# Adafruit_S-35710_Breakout.net
KiCad netlist of a schematic drawn in EAGLE
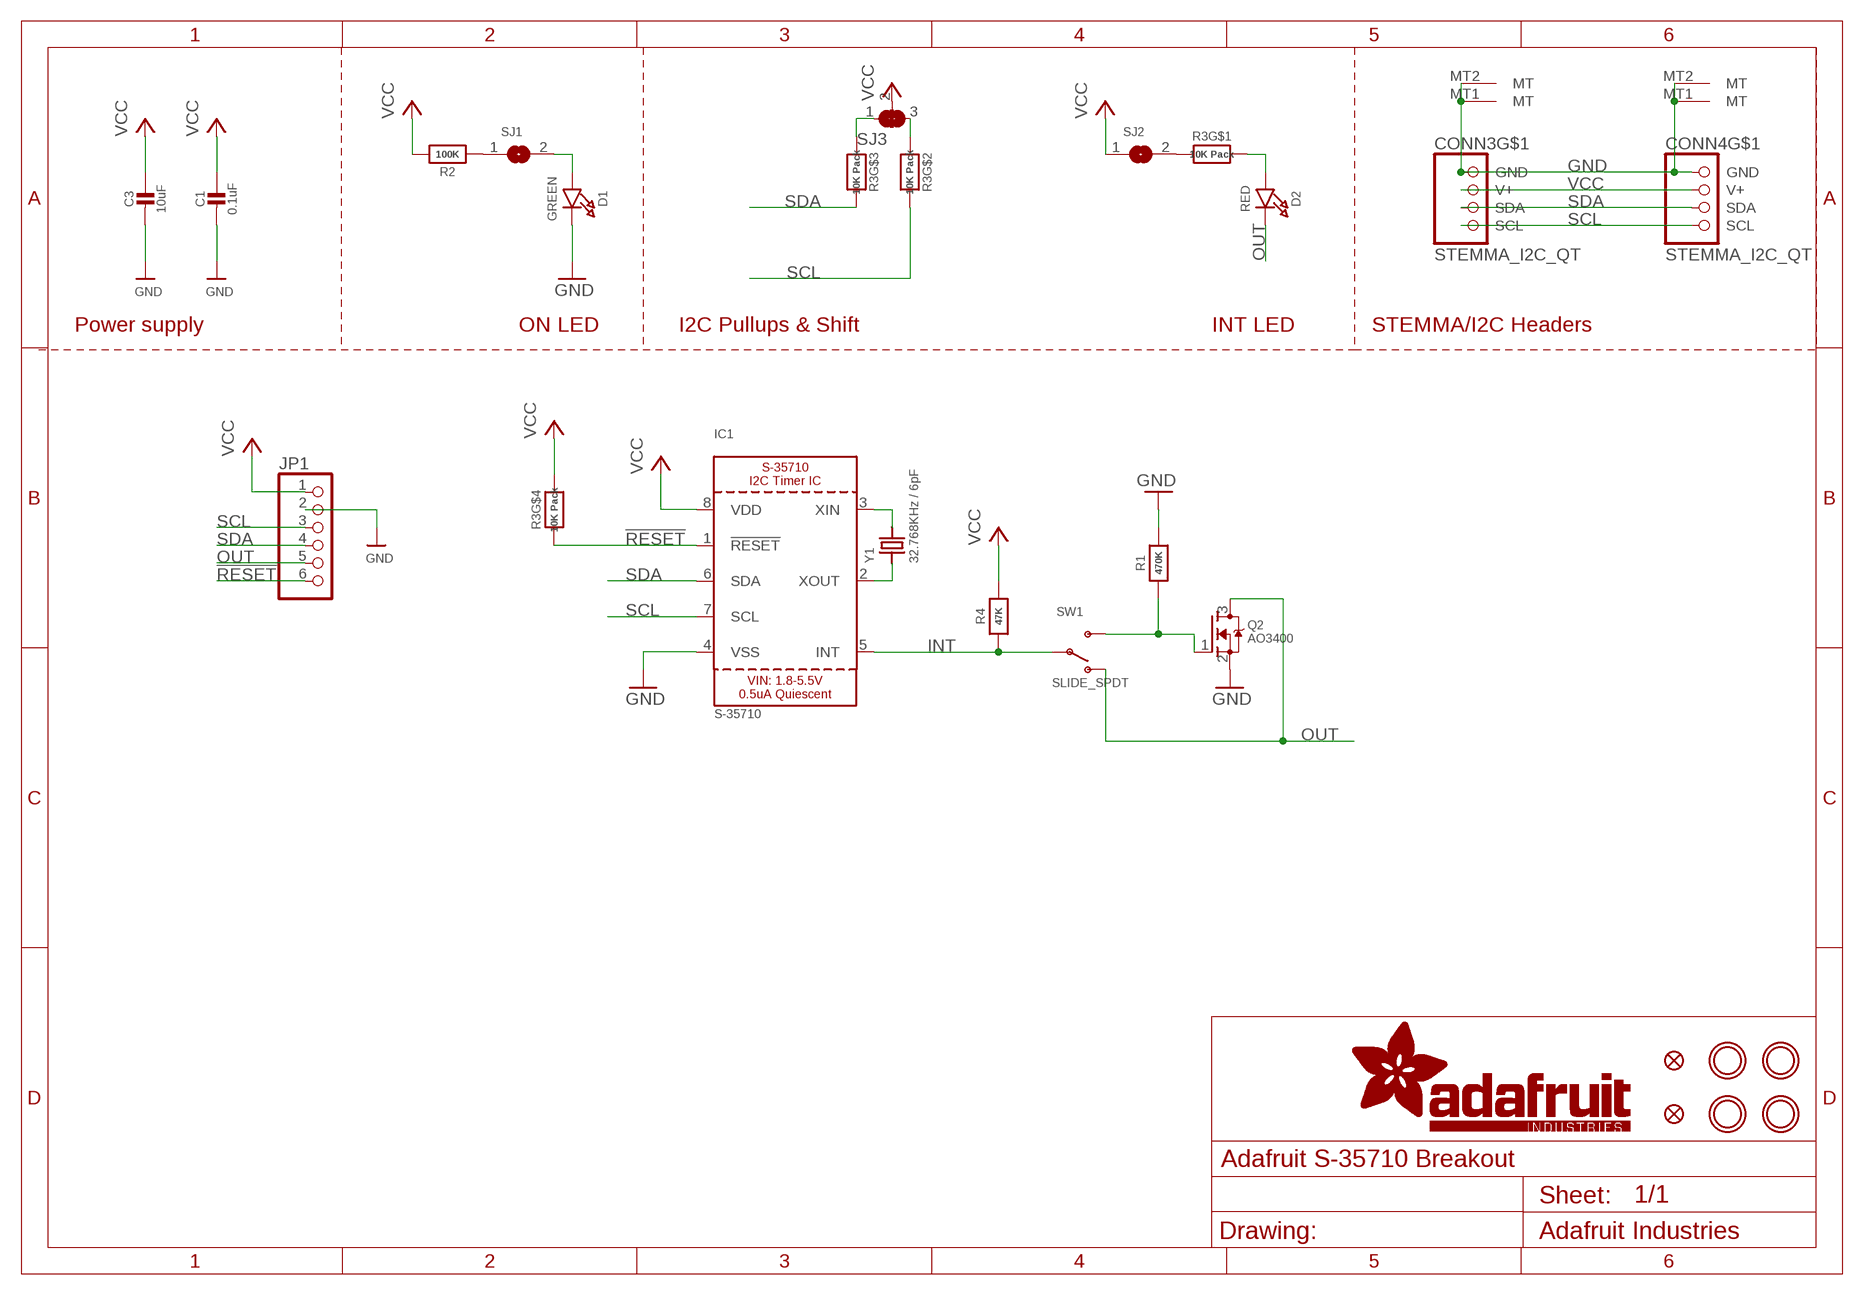
[diagram p0: schematic, sheet 1]

(export (version "E")
  (design (tool "Eeschema 10.0.6"))
  (components
    (comp (ref "C1")
      (value "0.1uF")
      (footprint "eagle-import:0603-NO")
      (libsource (lib "eagle-import") (part "CAP_CERAMIC0603_NO"))
    )
    (comp (ref "C3")
      (value "10uF")
      (footprint "eagle-import:0805-NO")
      (libsource (lib "eagle-import") (part "CAP_CERAMIC0805-NOOUTLINE"))
    )
    (comp (ref "CONN3")
      (value "STEMMA_I2C_QT")
      (footprint "eagle-import:JST_SH4")
      (libsource (lib "eagle-import") (part "STEMMA_I2C_QT"))
    )
    (comp (ref "CONN4")
      (value "STEMMA_I2C_QT")
      (footprint "eagle-import:JST_SH4")
      (libsource (lib "eagle-import") (part "STEMMA_I2C_QT"))
    )
    (comp (ref "D1")
      (value "GREEN")
      (footprint "eagle-import:CHIPLED_0603_NOOUTLINE")
      (libsource (lib "eagle-import") (part "LED0603_NOOUTLINE"))
    )
    (comp (ref "D2")
      (value "RED")
      (footprint "eagle-import:CHIPLED_0603_NOOUTLINE")
      (libsource (lib "eagle-import") (part "LED0603_NOOUTLINE"))
    )
    (comp (ref "FID3")
      (value "FIDUCIAL_1MM")
      (footprint "eagle-import:FIDUCIAL_1MM")
      (libsource (lib "eagle-import") (part "FIDUCIAL_1MM"))
    )
    (comp (ref "FID4")
      (value "FIDUCIAL_1MM")
      (footprint "eagle-import:FIDUCIAL_1MM")
      (libsource (lib "eagle-import") (part "FIDUCIAL_1MM"))
    )
    (comp (ref "IC1")
      (value "S-35710")
      (footprint "eagle-import:MSOP8_0.65MM")
      (libsource (lib "eagle-import") (part "S-35710"))
    )
    (comp (ref "JP1")
      (value "HEADER-1X670MIL")
      (footprint "eagle-import:1X06_ROUND_70")
      (libsource (lib "eagle-import") (part "HEADER-1X670MIL"))
    )
    (comp (ref "Q2")
      (value "AO3400")
      (footprint "eagle-import:SOT23-WIDE")
      (libsource (lib "eagle-import") (part "MOSFET-NWIDE"))
    )
    (comp (ref "R1")
      (value "470K")
      (footprint "eagle-import:0603-NO")
      (libsource (lib "eagle-import") (part "RESISTOR_0603_NOOUT"))
    )
    (comp (ref "R2")
      (value "100K")
      (footprint "eagle-import:0603-NO")
      (libsource (lib "eagle-import") (part "RESISTOR_0603_NOOUT"))
    )
    (comp (ref "R3")
      (value "10K Pack")
      (footprint "eagle-import:RESPACK_4X0603")
      (libsource (lib "eagle-import") (part "RESISTOR_4PACK"))
    )
    (comp (ref "R4")
      (value "47K")
      (footprint "eagle-import:0603-NO")
      (libsource (lib "eagle-import") (part "RESISTOR_0603_NOOUT"))
    )
    (comp (ref "SJ1")
      (value "SOLDERJUMPERCLOSED")
      (footprint "eagle-import:SOLDERJUMPER_CLOSEDWIRE")
      (libsource (lib "eagle-import") (part "SOLDERJUMPERCLOSED"))
    )
    (comp (ref "SJ2")
      (value "SOLDERJUMPERCLOSED")
      (footprint "eagle-import:SOLDERJUMPER_CLOSEDWIRE")
      (libsource (lib "eagle-import") (part "SOLDERJUMPERCLOSED"))
    )
    (comp (ref "SJ3")
      (value "SOLDERJUMPER_2WAY")
      (footprint "eagle-import:SOLDERJUMPER_2WAY_OPEN_NOPASTE")
      (libsource (lib "eagle-import") (part "SOLDERJUMPER_2WAY"))
    )
    (comp (ref "SW1")
      (value "SLIDE_SPDT")
      (footprint "eagle-import:SPDT_SMT_SSSS811101")
      (libsource (lib "eagle-import") (part "SWITCH_SPDT"))
    )
    (comp (ref "U$1")
      (value "MOUNTINGHOLE2.5")
      (footprint "eagle-import:MOUNTINGHOLE_2.5_PLATED")
      (libsource (lib "eagle-import") (part "MOUNTINGHOLE2.5"))
    )
    (comp (ref "U$17")
      (value "MOUNTINGHOLE2.5")
      (footprint "eagle-import:MOUNTINGHOLE_2.5_PLATED")
      (libsource (lib "eagle-import") (part "MOUNTINGHOLE2.5"))
    )
    (comp (ref "U$19")
      (value "MOUNTINGHOLE2.5")
      (footprint "eagle-import:MOUNTINGHOLE_2.5_PLATED")
      (libsource (lib "eagle-import") (part "MOUNTINGHOLE2.5"))
    )
    (comp (ref "U$21")
      (value "MOUNTINGHOLE2.5")
      (footprint "eagle-import:MOUNTINGHOLE_2.5_PLATED")
      (libsource (lib "eagle-import") (part "MOUNTINGHOLE2.5"))
    )
    (comp (ref "Y1")
      (value "32.768KHz / 6pF")
      (footprint "eagle-import:XTAL3215")
      (libsource (lib "eagle-import") (part "CRYSTAL_3215"))
    )
  )
  (nets
    (net (code "1") (name "/INT") (class "Default")
      (node (ref "IC1") (pin "5") (pinfunction "INT_5") (pintype "output"))
      (node (ref "R4") (pin "1") (pinfunction "1_1") (pintype "passive"))
      (node (ref "SW1") (pin "B") (pinfunction "P_B") (pintype "passive"))
    )
    (net (code "2") (name "/OUT") (class "Default")
      (node (ref "D2") (pin "C") (pinfunction "C_C") (pintype "passive"))
      (node (ref "JP1") (pin "5") (pinfunction "5_5") (pintype "passive"))
      (node (ref "Q2") (pin "3") (pinfunction "D_3") (pintype "bidirectional"))
      (node (ref "SW1") (pin "A") (pinfunction "O_A") (pintype "passive"))
    )
    (net (code "3") (name "/SCL") (class "Default")
      (node (ref "CONN3") (pin "4") (pinfunction "SCL_4") (pintype "passive"))
      (node (ref "CONN4") (pin "4") (pinfunction "SCL_4") (pintype "passive"))
      (node (ref "IC1") (pin "7") (pinfunction "SCL_7") (pintype "bidirectional"))
      (node (ref "JP1") (pin "3") (pinfunction "3_3") (pintype "passive"))
      (node (ref "R3") (pin "7") (pinfunction "2_7") (pintype "passive"))
    )
    (net (code "4") (name "/SDA") (class "Default")
      (node (ref "CONN3") (pin "3") (pinfunction "SDA_3") (pintype "passive"))
      (node (ref "CONN4") (pin "3") (pinfunction "SDA_3") (pintype "passive"))
      (node (ref "IC1") (pin "6") (pinfunction "SDA_6") (pintype "bidirectional"))
      (node (ref "JP1") (pin "4") (pinfunction "4_4") (pintype "passive"))
      (node (ref "R3") (pin "6") (pinfunction "2_6") (pintype "passive"))
    )
    (net (code "5") (name "/~{RESET}") (class "Default")
      (node (ref "IC1") (pin "1") (pinfunction "~{RESET}_1") (pintype "input"))
      (node (ref "JP1") (pin "6") (pinfunction "6_6") (pintype "passive"))
      (node (ref "R3") (pin "4") (pinfunction "1_4") (pintype "passive"))
    )
    (net (code "6") (name "GND") (class "Default")
      (node (ref "C1") (pin "2") (pinfunction "2_2") (pintype "passive"))
      (node (ref "C3") (pin "2") (pinfunction "2_2") (pintype "passive"))
      (node (ref "CONN3") (pin "1") (pinfunction "GND_1") (pintype "passive"))
      (node (ref "CONN3") (pin "MT1") (pinfunction "MT_MT1") (pintype "bidirectional"))
      (node (ref "CONN3") (pin "MT2") (pinfunction "MT_MT2") (pintype "bidirectional"))
      (node (ref "CONN4") (pin "1") (pinfunction "GND_1") (pintype "passive"))
      (node (ref "CONN4") (pin "MT1") (pinfunction "MT_MT1") (pintype "bidirectional"))
      (node (ref "CONN4") (pin "MT2") (pinfunction "MT_MT2") (pintype "bidirectional"))
      (node (ref "D1") (pin "C") (pinfunction "C_C") (pintype "passive"))
      (node (ref "IC1") (pin "4") (pinfunction "VSS_4") (pintype "power_in"))
      (node (ref "JP1") (pin "2") (pinfunction "2_2") (pintype "passive"))
      (node (ref "Q2") (pin "2") (pinfunction "S_2") (pintype "bidirectional"))
      (node (ref "R1") (pin "2") (pinfunction "2_2") (pintype "passive"))
    )
    (net (code "7") (name "Net-(D1-PadA)") (class "Default")
      (node (ref "D1") (pin "A") (pinfunction "A_A") (pintype "passive"))
      (node (ref "SJ1") (pin "2") (pinfunction "2_2") (pintype "passive"))
    )
    (net (code "8") (name "Net-(IC1-XIN)") (class "Default")
      (node (ref "IC1") (pin "3") (pinfunction "XIN_3") (pintype "input"))
      (node (ref "Y1") (pin "P$2") (pinfunction "2_P$2") (pintype "passive"))
    )
    (net (code "9") (name "Net-(IC1-XOUT)") (class "Default")
      (node (ref "IC1") (pin "2") (pinfunction "XOUT_2") (pintype "input"))
      (node (ref "Y1") (pin "P$1") (pinfunction "1_P$1") (pintype "passive"))
    )
    (net (code "10") (name "Net-(Q2-G)") (class "Default")
      (node (ref "Q2") (pin "1") (pinfunction "G_1") (pintype "bidirectional"))
      (node (ref "R1") (pin "1") (pinfunction "1_1") (pintype "passive"))
      (node (ref "SW1") (pin "C") (pinfunction "S_C") (pintype "passive"))
    )
    (net (code "11") (name "Net-(R2-Pad1)") (class "Default")
      (node (ref "R2") (pin "1") (pinfunction "1_1") (pintype "passive"))
      (node (ref "SJ1") (pin "1") (pinfunction "1_1") (pintype "passive"))
    )
    (net (code "12") (name "Net-(R3-Pad1)") (class "Default")
      (node (ref "R3") (pin "1") (pinfunction "1_1") (pintype "passive"))
      (node (ref "SJ2") (pin "2") (pinfunction "2_2") (pintype "passive"))
    )
    (net (code "13") (name "Net-(R3A-2)") (class "Default")
      (node (ref "D2") (pin "A") (pinfunction "A_A") (pintype "passive"))
      (node (ref "R3") (pin "8") (pinfunction "2_8") (pintype "passive"))
    )
    (net (code "14") (name "Net-(R3B-1)") (class "Default")
      (node (ref "R3") (pin "2") (pinfunction "1_2") (pintype "passive"))
      (node (ref "SJ3") (pin "3") (pinfunction "3_3") (pintype "passive"))
    )
    (net (code "15") (name "Net-(R3C-1)") (class "Default")
      (node (ref "R3") (pin "3") (pinfunction "1_3") (pintype "passive"))
      (node (ref "SJ3") (pin "1") (pinfunction "1_1") (pintype "passive"))
    )
    (net (code "16") (name "VCC") (class "Default")
      (node (ref "C1") (pin "1") (pinfunction "1_1") (pintype "passive"))
      (node (ref "C3") (pin "1") (pinfunction "1_1") (pintype "passive"))
      (node (ref "CONN3") (pin "2") (pinfunction "V+_2") (pintype "passive"))
      (node (ref "CONN4") (pin "2") (pinfunction "V+_2") (pintype "passive"))
      (node (ref "IC1") (pin "8") (pinfunction "VDD_8") (pintype "power_in"))
      (node (ref "JP1") (pin "1") (pinfunction "1_1") (pintype "passive"))
      (node (ref "R2") (pin "2") (pinfunction "2_2") (pintype "passive"))
      (node (ref "R3") (pin "5") (pinfunction "2_5") (pintype "passive"))
      (node (ref "R4") (pin "2") (pinfunction "2_2") (pintype "passive"))
      (node (ref "SJ2") (pin "1") (pinfunction "1_1") (pintype "passive"))
      (node (ref "SJ3") (pin "2") (pinfunction "2_2") (pintype "passive"))
    )
  )
)
